# SCH_nfc_card_2025-04-15.net
KiCad netlist of a schematic drawn in EasyEDA
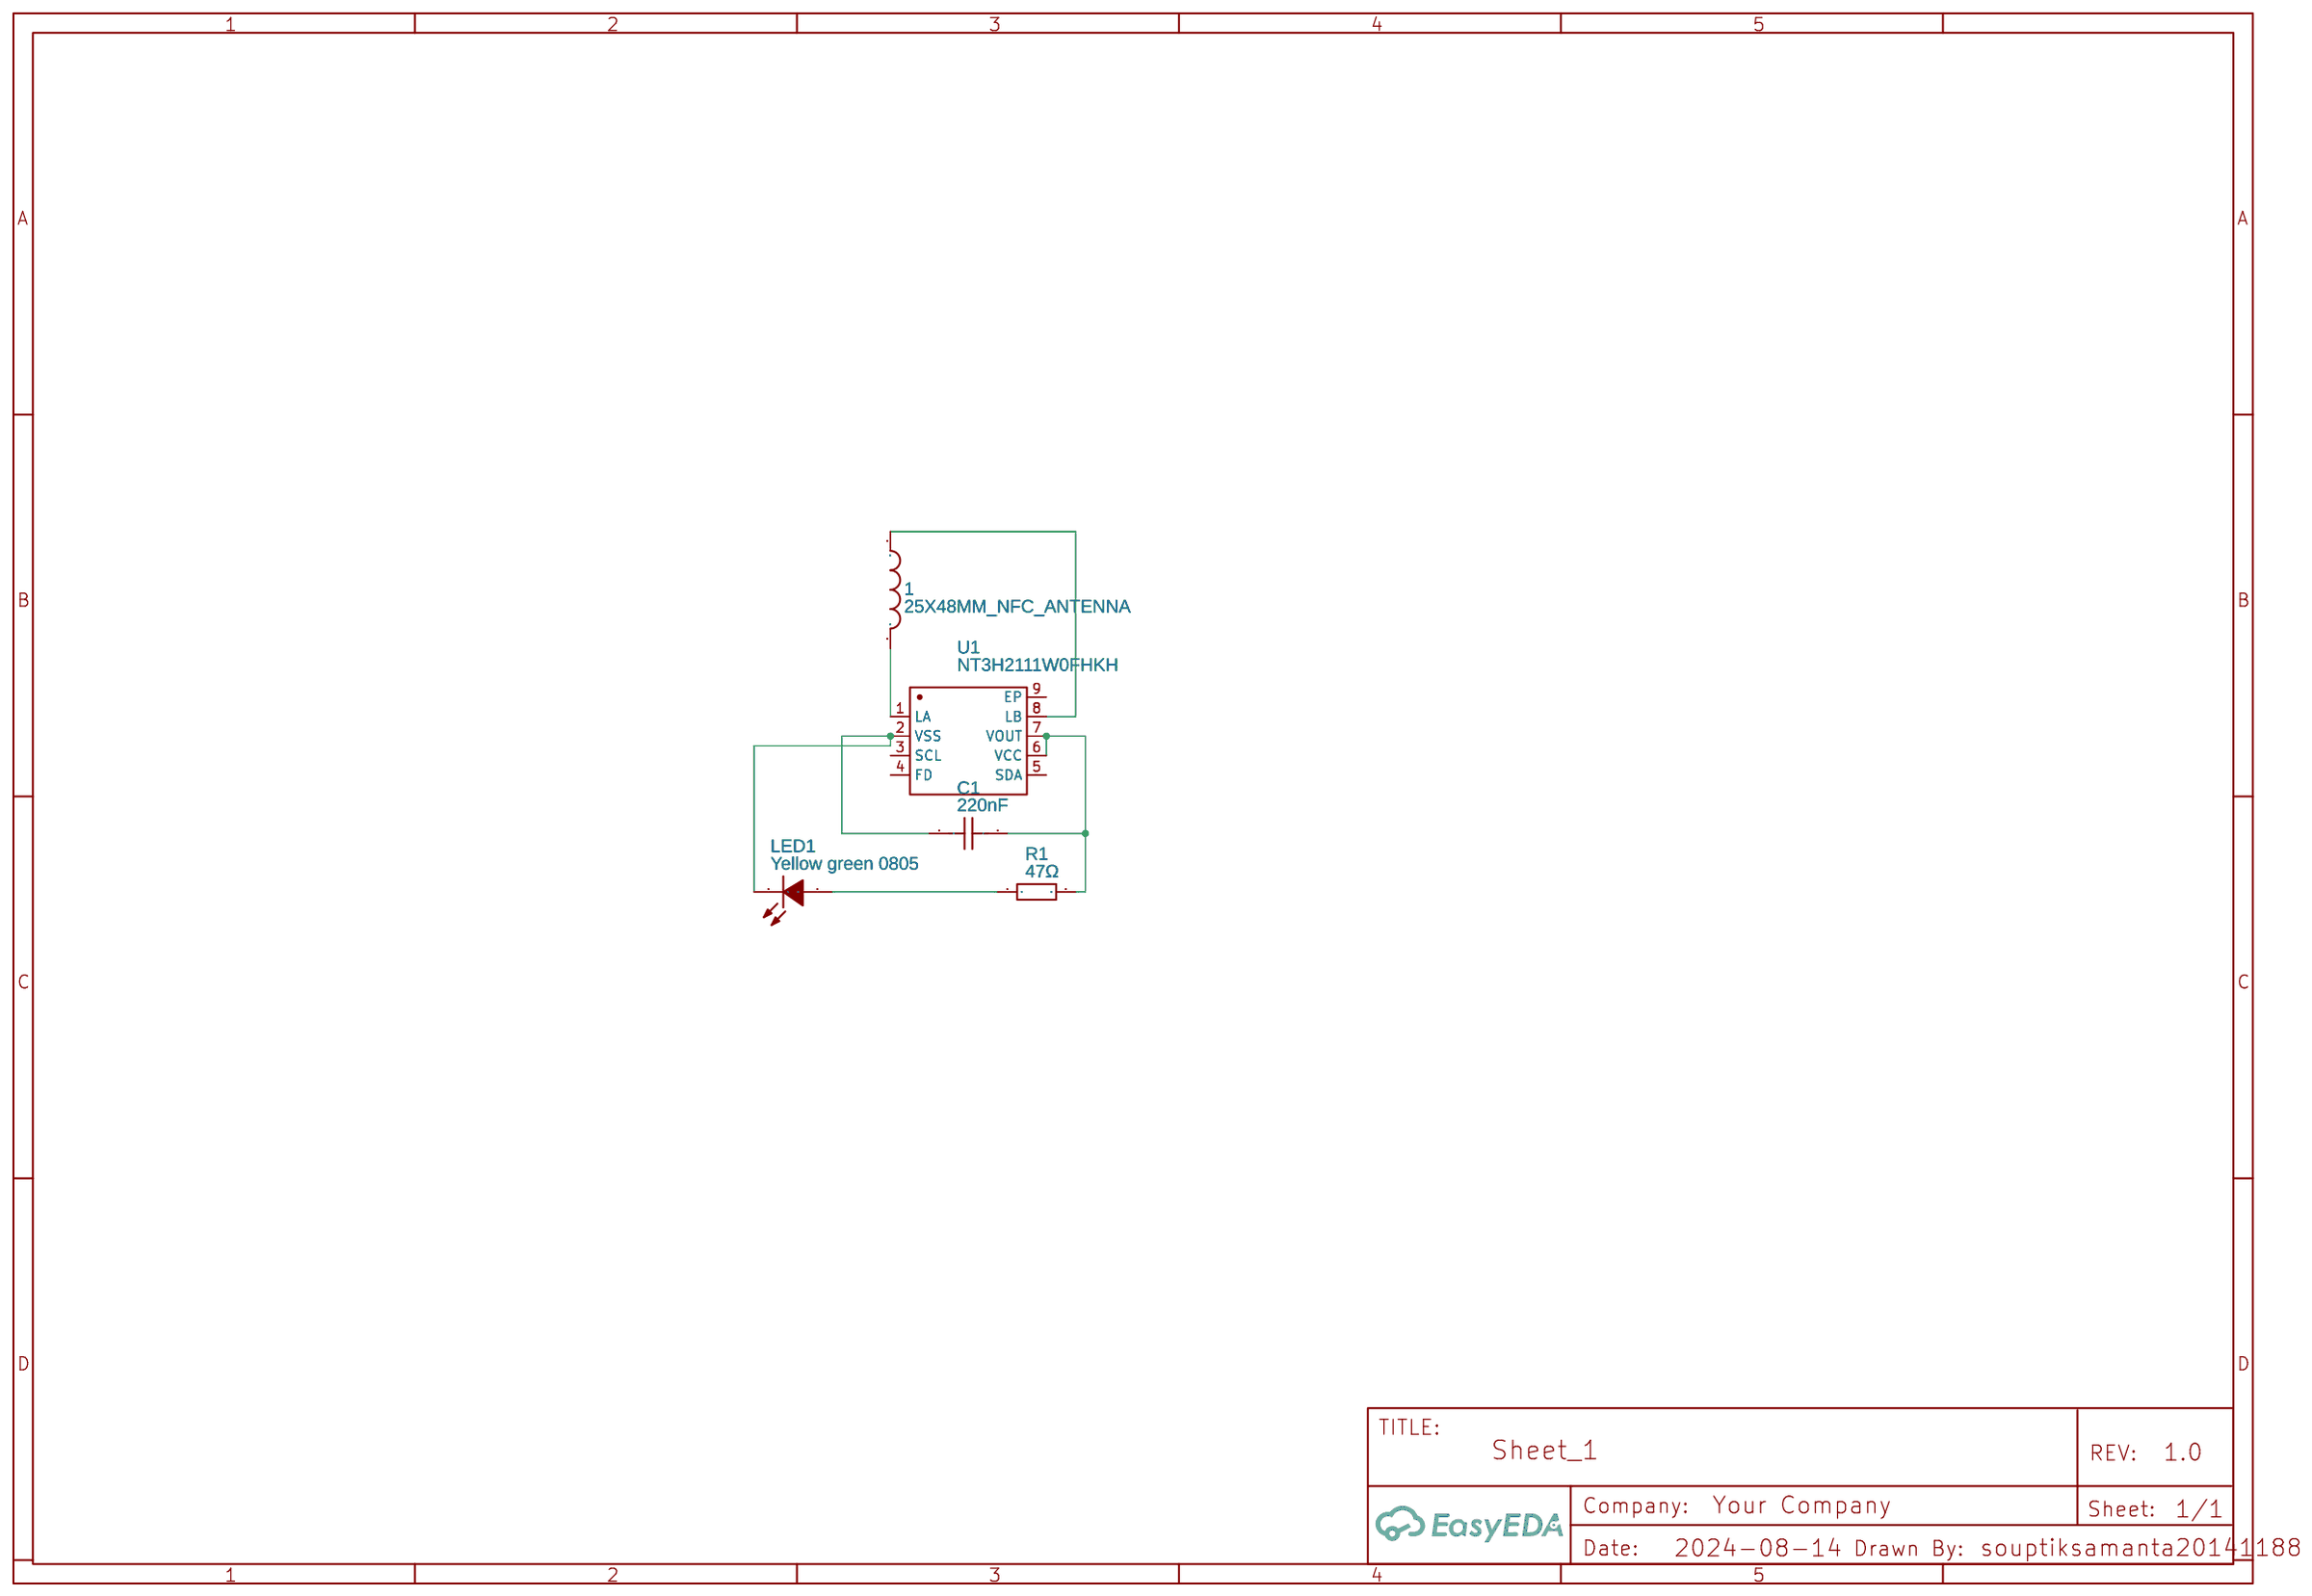
[diagram p0: schematic sheet]

(export (version "E")
  (design (tool "Eeschema 10.0.6"))
  (components
    (comp (ref "1") (value "25X48MM_NFC_ANTENNA") (libsource (lib "") (part "25X48MM_NFC_ANTENNA")))
    (comp (ref "C1")
      (value "220nF")
      (fields (field (name "Manufacturer Part") "0805B224K500NT") (field (name "Manufacturer") "FH(风华)"))
      (libsource (lib "") (part "0805B224K500NT"))
    )
    (comp (ref "LED1")
      (value "Yellow green 0805")
      (fields (field (name "Manufacturer Part") "KT-0805YG") (field (name "Manufacturer") "KENTO"))
      (libsource (lib "") (part "Yellow green 0805"))
    )
    (comp (ref "R1")
      (value "47Ω")
      (fields
        (field (name "Manufacturer Part") "0603WAF470JT5E")
        (field (name "Manufacturer") "UNI-ROYAL(厚声)")
      )
      (libsource (lib "") (part "0603WAF470JT5E"))
    )
    (comp (ref "U1")
      (value "NT3H2111W0FHKH")
      (fields (field (name "Manufacturer") "NXP(恩智浦)"))
      (libsource (lib "") (part "NT3H2111W0FHKH"))
    )
  )
  (nets
    (net (code "1") (name "Net-(LED1-A)") (class "Default")
      (node (ref "LED1") (pin "1") (pinfunction "A_1") (pintype "unspecified"))
      (node (ref "R1") (pin "1") (pinfunction "1_1") (pintype "input"))
    )
    (net (code "2") (name "Net-(LED1-K)") (class "Default")
      (node (ref "C1") (pin "2") (pinfunction "2_2") (pintype "unspecified"))
      (node (ref "LED1") (pin "2") (pinfunction "K_2") (pintype "unspecified"))
      (node (ref "U1") (pin "2") (pinfunction "VSS_2") (pintype "unspecified"))
    )
    (net (code "3") (name "Net-(U1-LA)") (class "Default")
      (node (ref "1") (pin "P$2") (pinfunction "P$2_P$2") (pintype "bidirectional"))
      (node (ref "U1") (pin "1") (pinfunction "LA_1") (pintype "unspecified"))
    )
    (net (code "4") (name "Net-(U1-LB)") (class "Default")
      (node (ref "1") (pin "P$1") (pinfunction "P$1_P$1") (pintype "bidirectional"))
      (node (ref "U1") (pin "8") (pinfunction "LB_8") (pintype "unspecified"))
    )
    (net (code "5") (name "Net-(U1-VCC)") (class "Default")
      (node (ref "C1") (pin "1") (pinfunction "1_1") (pintype "unspecified"))
      (node (ref "R1") (pin "2") (pinfunction "2_2") (pintype "input"))
      (node (ref "U1") (pin "6") (pinfunction "VCC_6") (pintype "unspecified"))
      (node (ref "U1") (pin "7") (pinfunction "VOUT_7") (pintype "unspecified"))
    )
    (net (code "6") (name "unconnected-(U1-EP-Pad9)") (class "Default")
      (node (ref "U1") (pin "9") (pinfunction "EP_9") (pintype "unspecified"))
    )
    (net (code "7") (name "unconnected-(U1-FD-Pad4)") (class "Default")
      (node (ref "U1") (pin "4") (pinfunction "FD_4") (pintype "unspecified"))
    )
    (net (code "8") (name "unconnected-(U1-SCL-Pad3)") (class "Default")
      (node (ref "U1") (pin "3") (pinfunction "SCL_3") (pintype "unspecified"))
    )
    (net (code "9") (name "unconnected-(U1-SDA-Pad5)") (class "Default")
      (node (ref "U1") (pin "5") (pinfunction "SDA_5") (pintype "unspecified"))
    )
  )
)
